# HDMI_Connector.net
KiCad netlist of a schematic drawn in Altium Designer
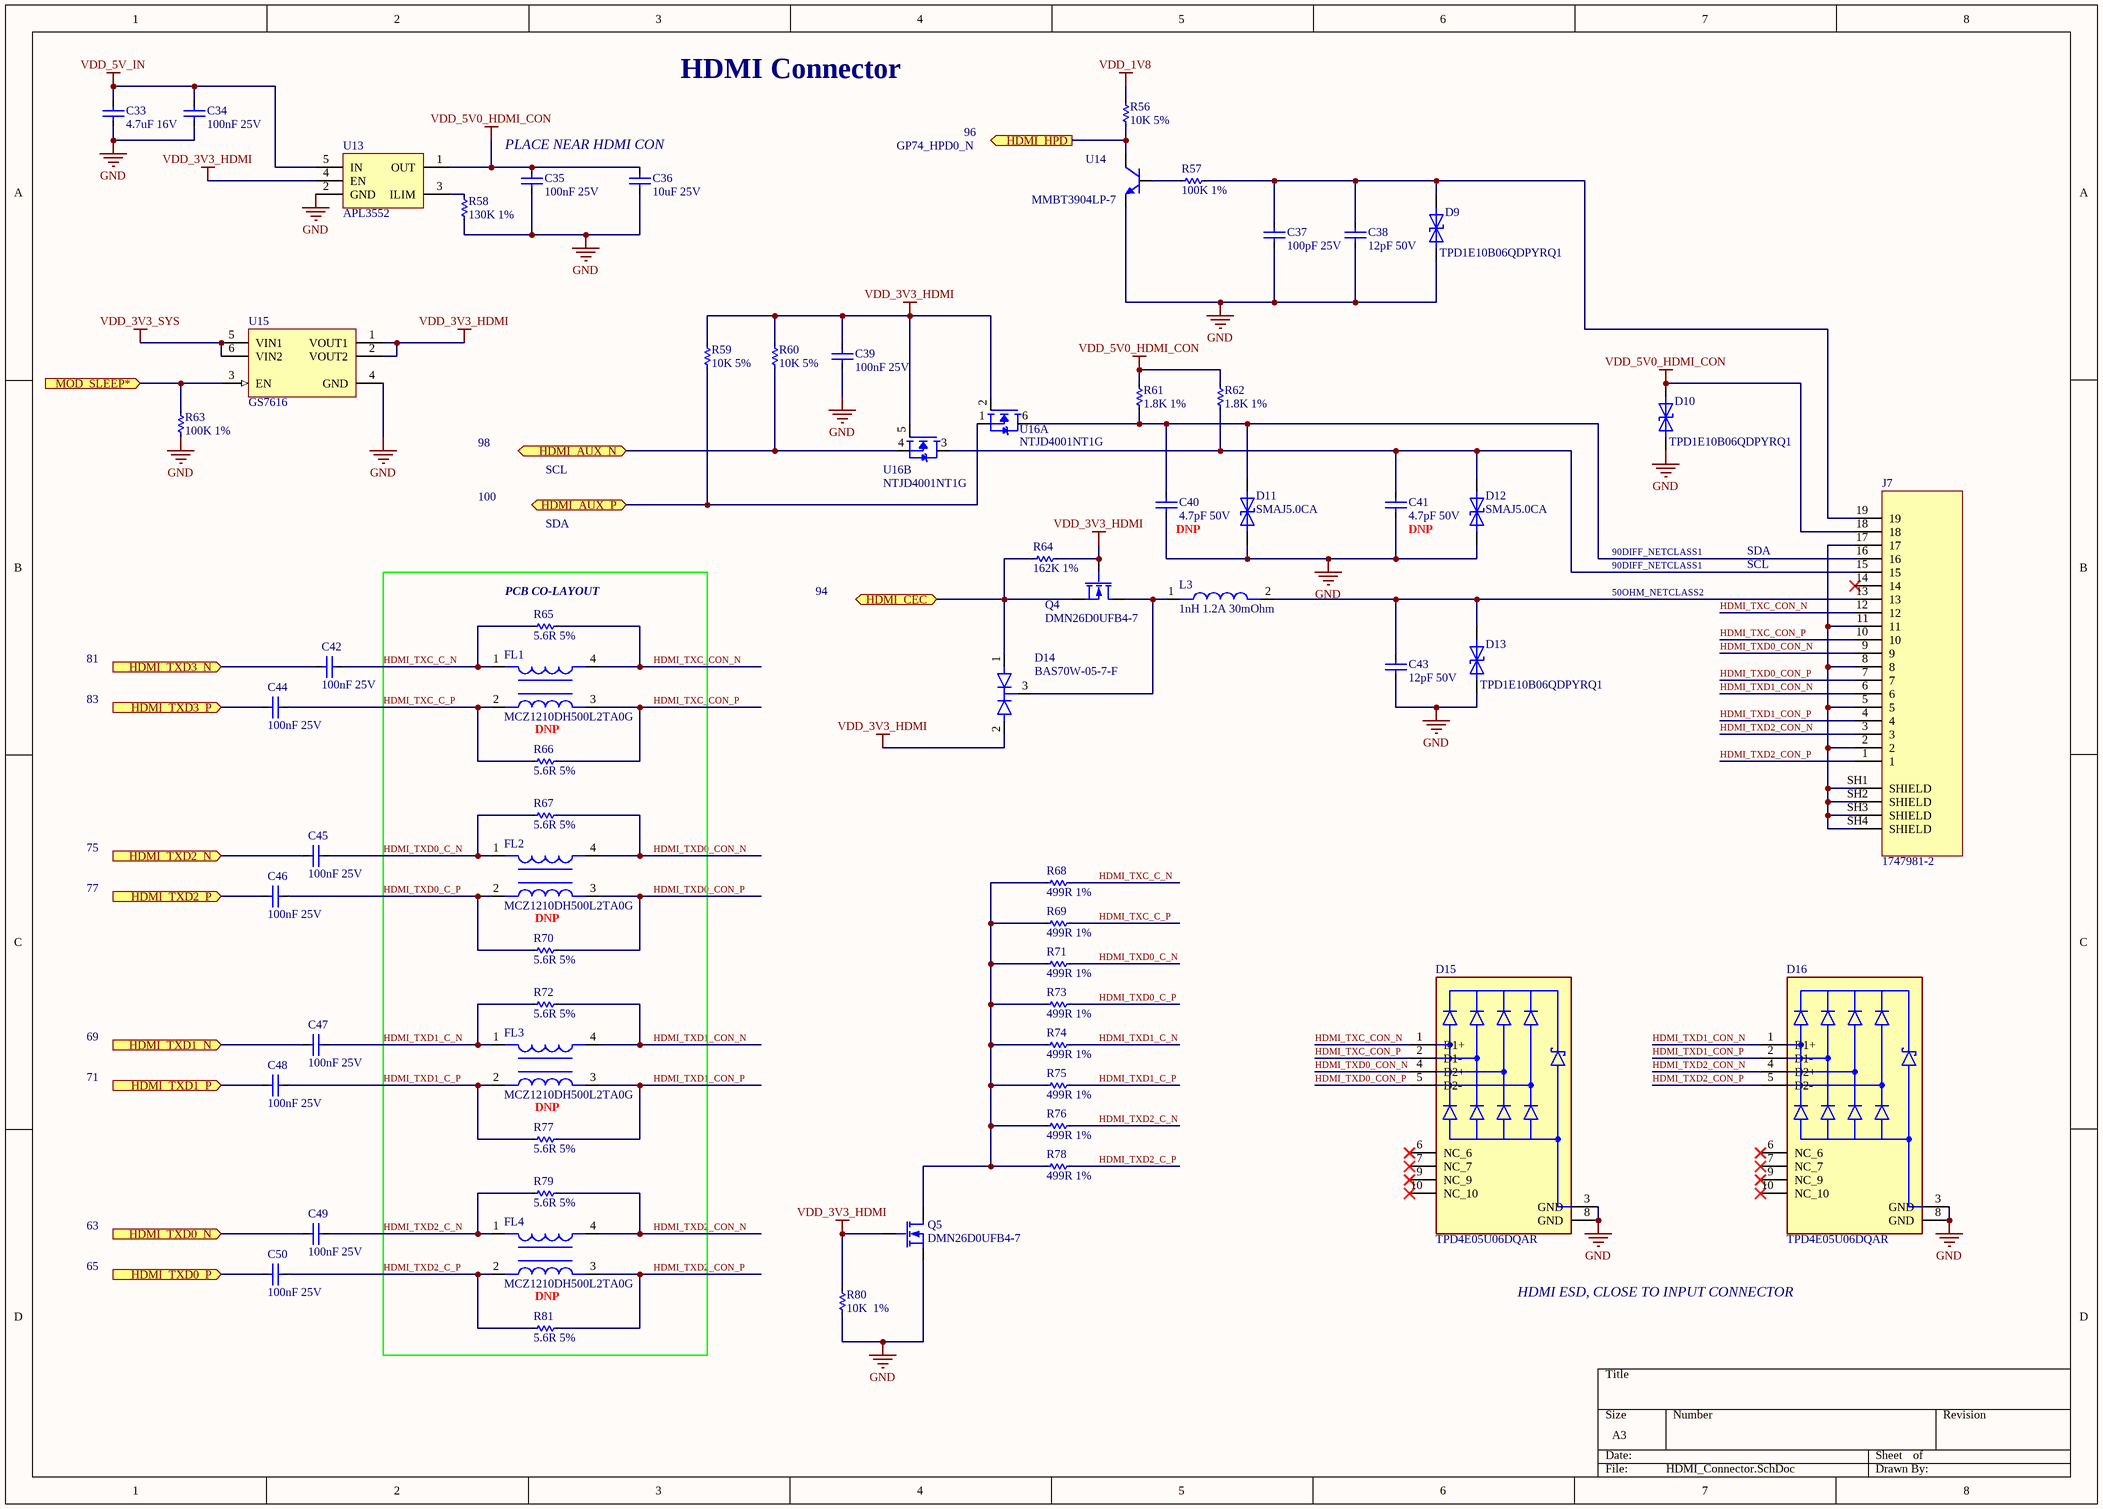
[diagram p0: HDMI_Connector.SchDoc]

(export (version "E")
  (design (tool "Eeschema 10.0.6"))
  (components
    (comp (ref "C33")
      (value "4.7uF 16V")
      (footprint "C0805")
      (description "CAP CER 4.7UF 16V X5R 0805")
      (fields
        (field (name "MANUFACTURER") "Kyocera AVX")
        (field (name "MANUFACTURER PART NUMBER") "0805YD475KAT2A")
      )
      (libsource (lib "GM_Altium_Library") (part "0805YD475KAT2A"))
    )
    (comp (ref "C34")
      (value "100nF 25V")
      (footprint "C0402")
      (description "0402 100 nF 25 V ±10 % Tolerance X7R Surface Mount Multilayer Ceramic Capacitor")
      (fields
        (field (name "MANUFACTURER") "Kyocera AVX")
        (field (name "MANUFACTURER PART NUMBER") "04023C104KAT2A")
      )
      (libsource (lib "GM_Altium_Library") (part "04023C104KAT2A"))
    )
    (comp (ref "C35")
      (value "100nF 25V")
      (footprint "C0402")
      (description "0402 100 nF 25 V ±10 % Tolerance X7R Surface Mount Multilayer Ceramic Capacitor")
      (fields
        (field (name "MANUFACTURER") "Kyocera AVX")
        (field (name "MANUFACTURER PART NUMBER") "04023C104KAT2A")
      )
      (libsource (lib "GM_Altium_Library") (part "04023C104KAT2A"))
    )
    (comp (ref "C36")
      (value "10uF 25V")
      (footprint "C0805")
      (description "0805 10 uF 25 V ±10% Tolerance X5R SMT Multilayer Ceramic Capacitor")
      (fields
        (field (name "MANUFACTURER") "Taiyo Yuden")
        (field (name "MANUFACTURER PART NUMBER") "TMK212BBJ106KG-T")
      )
      (libsource (lib "GM_Altium_Library") (part "TMK212BBJ106KG-T"))
    )
    (comp (ref "C37")
      (value "100pF 25V")
      (footprint "C0402")
      (description "Cap Ceramic 100pF 25V C0G 5% SMD 0402 125C Paper T/R")
      (fields
        (field (name "MANUFACTURER") "KEMET")
        (field (name "MANUFACTURER PART NUMBER") "C0402C101J3GACTU")
      )
      (libsource (lib "GM_Altium_Library") (part "C0402C101J3GACTU"))
    )
    (comp (ref "C38")
      (value "12pF 50V")
      (footprint "C0402")
      (description "0402 12 pF 50 V ±5 % Tolerance NP0 SMT Multilayer Ceramic Capacitor")
      (fields
        (field (name "MANUFACTURER") "Yageo")
        (field (name "MANUFACTURER PART NUMBER") "CC0402JRNPO9BN120")
      )
      (libsource (lib "GM_Altium_Library") (part "CC0402JRNPO9BN120"))
    )
    (comp (ref "C39")
      (value "100nF 25V")
      (footprint "C0402")
      (description "CAP CER 0.1UF 25V X5R 0402 / High Value Multilayer Ceramic Capacitors (High dielectric type)")
      (fields
        (field (name "MANUFACTURER") "Taiyo Yuden")
        (field (name "MANUFACTURER PART NUMBER") "TMK105BJ104KV-F")
      )
      (libsource (lib "GM_Altium_Library") (part "TMK105BJ104KV-F"))
    )
    (comp (ref "C40")
      (value "4.7pF 50V")
      (footprint "C0402")
      (description "Surface Mount Ceramic Multilayer Capacitor 4.7pF 0.25pF C0G 50V 0402 Paper T/R")
      (fields
        (field (name "MANUFACTURER") "Yageo")
        (field (name "MANUFACTURER PART NUMBER") "CC0402CRNPO9BN4R7")
      )
      (libsource (lib "GM_Altium_Library") (part "CC0402CRNPO9BN4R7"))
    )
    (comp (ref "C41")
      (value "4.7pF 50V")
      (footprint "C0402")
      (description "Surface Mount Ceramic Multilayer Capacitor 4.7pF 0.25pF C0G 50V 0402 Paper T/R")
      (fields
        (field (name "MANUFACTURER") "Yageo")
        (field (name "MANUFACTURER PART NUMBER") "CC0402CRNPO9BN4R7")
      )
      (libsource (lib "GM_Altium_Library") (part "CC0402CRNPO9BN4R7"))
    )
    (comp (ref "C42")
      (value "100nF 25V")
      (footprint "C0402")
      (description "0402 100 nF 25 V ±10 % Tolerance X7R Surface Mount Multilayer Ceramic Capacitor")
      (fields
        (field (name "MANUFACTURER") "Kyocera AVX")
        (field (name "MANUFACTURER PART NUMBER") "04023C104KAT2A")
      )
      (libsource (lib "GM_Altium_Library") (part "04023C104KAT2A"))
    )
    (comp (ref "C43")
      (value "12pF 50V")
      (footprint "C0402")
      (description "0402 12 pF 50 V ±5 % Tolerance NP0 SMT Multilayer Ceramic Capacitor")
      (fields
        (field (name "MANUFACTURER") "Yageo")
        (field (name "MANUFACTURER PART NUMBER") "CC0402JRNPO9BN120")
      )
      (libsource (lib "GM_Altium_Library") (part "CC0402JRNPO9BN120"))
    )
    (comp (ref "C44")
      (value "100nF 25V")
      (footprint "C0402")
      (description "0402 100 nF 25 V ±10 % Tolerance X7R Surface Mount Multilayer Ceramic Capacitor")
      (fields
        (field (name "MANUFACTURER") "Kyocera AVX")
        (field (name "MANUFACTURER PART NUMBER") "04023C104KAT2A")
      )
      (libsource (lib "GM_Altium_Library") (part "04023C104KAT2A"))
    )
    (comp (ref "C45")
      (value "100nF 25V")
      (footprint "C0402")
      (description "0402 100 nF 25 V ±10 % Tolerance X7R Surface Mount Multilayer Ceramic Capacitor")
      (fields
        (field (name "MANUFACTURER") "Kyocera AVX")
        (field (name "MANUFACTURER PART NUMBER") "04023C104KAT2A")
      )
      (libsource (lib "GM_Altium_Library") (part "04023C104KAT2A"))
    )
    (comp (ref "C46")
      (value "100nF 25V")
      (footprint "C0402")
      (description "0402 100 nF 25 V ±10 % Tolerance X7R Surface Mount Multilayer Ceramic Capacitor")
      (fields
        (field (name "MANUFACTURER") "Kyocera AVX")
        (field (name "MANUFACTURER PART NUMBER") "04023C104KAT2A")
      )
      (libsource (lib "GM_Altium_Library") (part "04023C104KAT2A"))
    )
    (comp (ref "C47")
      (value "100nF 25V")
      (footprint "C0402")
      (description "0402 100 nF 25 V ±10 % Tolerance X7R Surface Mount Multilayer Ceramic Capacitor")
      (fields
        (field (name "MANUFACTURER") "Kyocera AVX")
        (field (name "MANUFACTURER PART NUMBER") "04023C104KAT2A")
      )
      (libsource (lib "GM_Altium_Library") (part "04023C104KAT2A"))
    )
    (comp (ref "C48")
      (value "100nF 25V")
      (footprint "C0402")
      (description "0402 100 nF 25 V ±10 % Tolerance X7R Surface Mount Multilayer Ceramic Capacitor")
      (fields
        (field (name "MANUFACTURER") "Kyocera AVX")
        (field (name "MANUFACTURER PART NUMBER") "04023C104KAT2A")
      )
      (libsource (lib "GM_Altium_Library") (part "04023C104KAT2A"))
    )
    (comp (ref "C49")
      (value "100nF 25V")
      (footprint "C0402")
      (description "0402 100 nF 25 V ±10 % Tolerance X7R Surface Mount Multilayer Ceramic Capacitor")
      (fields
        (field (name "MANUFACTURER") "Kyocera AVX")
        (field (name "MANUFACTURER PART NUMBER") "04023C104KAT2A")
      )
      (libsource (lib "GM_Altium_Library") (part "04023C104KAT2A"))
    )
    (comp (ref "C50")
      (value "100nF 25V")
      (footprint "C0402")
      (description "0402 100 nF 25 V ±10 % Tolerance X7R Surface Mount Multilayer Ceramic Capacitor")
      (fields
        (field (name "MANUFACTURER") "Kyocera AVX")
        (field (name "MANUFACTURER PART NUMBER") "04023C104KAT2A")
      )
      (libsource (lib "GM_Altium_Library") (part "04023C104KAT2A"))
    )
    (comp (ref "D9")
      (value "TPD1E10B06QDPYRQ1")
      (footprint "2-X1SON (1x.60)")
      (description "Automotive 12-pF, ±5.5V ±30-kV ESD protection diode in 0402 Package 2-X1SON -40 to 125")
      (fields (field (name "MANUFACTURER") "Texas Instruments"))
      (libsource (lib "GM_Altium_Library") (part "TPD1E10B06QDPYRQ1"))
    )
    (comp (ref "D10")
      (value "TPD1E10B06QDPYRQ1")
      (footprint "2-X1SON (1x.60)")
      (description "Automotive 12-pF, ±5.5V ±30-kV ESD protection diode in 0402 Package 2-X1SON -40 to 125")
      (fields (field (name "MANUFACTURER") "Texas Instruments"))
      (libsource (lib "GM_Altium_Library") (part "TPD1E10B06QDPYRQ1"))
    )
    (comp (ref "D11")
      (value "SMAJ5.0CA")
      (footprint "DO-214AC")
      (fields (field (name "MANUFACTURER") "Littelfuse"))
      (libsource (lib "GM_Altium_Library") (part "SMAJ5.0CA"))
    )
    (comp (ref "D12")
      (value "SMAJ5.0CA")
      (footprint "DO-214AC")
      (fields (field (name "MANUFACTURER") "Littelfuse"))
      (libsource (lib "GM_Altium_Library") (part "SMAJ5.0CA"))
    )
    (comp (ref "D13")
      (value "TPD1E10B06QDPYRQ1")
      (footprint "2-X1SON (1x.60)")
      (description "Automotive 12-pF, ±5.5V ±30-kV ESD protection diode in 0402 Package 2-X1SON -40 to 125")
      (fields (field (name "MANUFACTURER") "Texas Instruments"))
      (libsource (lib "GM_Altium_Library") (part "TPD1E10B06QDPYRQ1"))
    )
    (comp (ref "D14")
      (value "BAS70W-05-7-F")
      (footprint "SOT-323")
      (description "DIODE ARRAY SCHOTTKY 70V SOT323")
      (fields (field (name "MANUFACTURER") "Diodes"))
      (libsource (lib "GM_Altium_Library") (part "BAS70W-05-7-F"))
    )
    (comp (ref "D15")
      (value "TPD4E05U06DQAR")
      (footprint "TPD4E05U06DQAR")
      (description "Quad 0.5-pF, 5.5-V, ±12-kV ESD protection diode for USB, HDMI & High Speed Interfaces")
      (fields (field (name "MANUFACTURER") "Texas Instruments"))
      (libsource (lib "GM_Altium_Library") (part "TPD4E05U06DQAR"))
    )
    (comp (ref "D16")
      (value "TPD4E05U06DQAR")
      (footprint "TPD4E05U06DQAR")
      (description "Quad 0.5-pF, 5.5-V, ±12-kV ESD protection diode for USB, HDMI & High Speed Interfaces")
      (fields (field (name "MANUFACTURER") "Texas Instruments"))
      (libsource (lib "GM_Altium_Library") (part "TPD4E05U06DQAR"))
    )
    (comp (ref "FL1")
      (value "MCZ1210DH500L2TA0G")
      (footprint "MCZ1210DH500L2TA0G")
      (description "2 Line Common Mode Choke Surface Mount 50 Ohms 100mA DCR 2.5Ohm")
      (fields (field (name "MANUFACTURER") "TDK"))
      (libsource (lib "GM_Altium_Library") (part "MCZ1210DH500L2TA0G"))
    )
    (comp (ref "FL2")
      (value "MCZ1210DH500L2TA0G")
      (footprint "MCZ1210DH500L2TA0G")
      (description "2 Line Common Mode Choke Surface Mount 50 Ohms 100mA DCR 2.5Ohm")
      (fields (field (name "MANUFACTURER") "TDK"))
      (libsource (lib "GM_Altium_Library") (part "MCZ1210DH500L2TA0G"))
    )
    (comp (ref "FL3")
      (value "MCZ1210DH500L2TA0G")
      (footprint "MCZ1210DH500L2TA0G")
      (description "2 Line Common Mode Choke Surface Mount 50 Ohms 100mA DCR 2.5Ohm")
      (fields (field (name "MANUFACTURER") "TDK"))
      (libsource (lib "GM_Altium_Library") (part "MCZ1210DH500L2TA0G"))
    )
    (comp (ref "FL4")
      (value "MCZ1210DH500L2TA0G")
      (footprint "MCZ1210DH500L2TA0G")
      (description "2 Line Common Mode Choke Surface Mount 50 Ohms 100mA DCR 2.5Ohm")
      (fields (field (name "MANUFACTURER") "TDK"))
      (libsource (lib "GM_Altium_Library") (part "MCZ1210DH500L2TA0G"))
    )
    (comp (ref "J7")
      (value "1747981-2")
      (footprint "1747981-2")
      (description "Conn HDMI RCP 19 POS 0.5mm Solder ST SMD 19 Terminal 1 Port T/R")
      (fields (field (name "MANUFACTURER") "TE Connectivity"))
      (libsource (lib "GM_Altium_Library") (part "1747981-2"))
    )
    (comp (ref "L3")
      (value "1nH 1.2A 30mOhm")
      (footprint "L0402")
      (description "Inductor Chip 1nH 0.1nH Tolerance 2-Pin 0402 Paper T/R")
      (fields
        (field (name "MANUFACTURER") "Murata")
        (field (name "MANUFACTURER PART NUMBER") "LQG15WH1N0B02D")
      )
      (libsource (lib "GM_Altium_Library") (part "LQG15WH1N0B02D"))
    )
    (comp (ref "Q4")
      (value "DMN26D0UFB4-7")
      (footprint "DFN1006-3")
      (description "Single N-Channel 20 V 350 mW Silicon Surface Mount Mosfet - DFN-3")
      (fields (field (name "MANUFACTURER") "Diodes"))
      (libsource (lib "GM_Altium_Library") (part "DMN26D0UFB4-7"))
    )
    (comp (ref "Q5")
      (value "DMN26D0UFB4-7")
      (footprint "DFN1006-3")
      (description "Single N-Channel 20 V 350 mW Silicon Surface Mount Mosfet - DFN-3")
      (fields (field (name "MANUFACTURER") "Diodes"))
      (libsource (lib "GM_Altium_Library") (part "DMN26D0UFB4-7"))
    )
    (comp (ref "R56")
      (value "10K 5%")
      (footprint "R0402")
      (description "Res Thick Film 0402 10K Ohm 5% 0.063W(1/16W) ±100ppm/C Pad SMD T/R")
      (fields
        (field (name "MANUFACTURER") "Yageo")
        (field (name "MANUFACTURER PART NUMBER") "RC0402JR-0710KL")
      )
      (libsource (lib "GM_Altium_Library") (part "RC0402JR-0710KL"))
    )
    (comp (ref "R57")
      (value "100K 1%")
      (footprint "R0402")
      (description "RES SMD 100K OHM 1% 1/16W 0402")
      (fields
        (field (name "MANUFACTURER") "Yageo")
        (field (name "MANUFACTURER PART NUMBER") "RC0402FR-07100KL")
      )
      (libsource (lib "GM_Altium_Library") (part "RC0402FR-07100KL"))
    )
    (comp (ref "R58")
      (value "130K 1%")
      (footprint "R0402")
      (description "Res General Purpose Thick Film 0402 130k Ohm 1% 1/16W ±100ppm/°C Molded Paper T/R")
      (fields
        (field (name "MANUFACTURER") "Yageo")
        (field (name "MANUFACTURER PART NUMBER") "RC0402FR-07130KL")
      )
      (libsource (lib "GM_Altium_Library") (part "RC0402FR-07130KL"))
    )
    (comp (ref "R59")
      (value "10K 5%")
      (footprint "R0402")
      (description "Res Thick Film 0402 10K Ohm 5% 0.063W(1/16W) ±100ppm/C Pad SMD T/R")
      (fields
        (field (name "MANUFACTURER") "Yageo")
        (field (name "MANUFACTURER PART NUMBER") "RC0402JR-0710KL")
      )
      (libsource (lib "GM_Altium_Library") (part "RC0402JR-0710KL"))
    )
    (comp (ref "R60")
      (value "10K 5%")
      (footprint "R0402")
      (description "Res Thick Film 0402 10K Ohm 5% 0.063W(1/16W) ±100ppm/C Pad SMD T/R")
      (fields
        (field (name "MANUFACTURER") "Yageo")
        (field (name "MANUFACTURER PART NUMBER") "RC0402JR-0710KL")
      )
      (libsource (lib "GM_Altium_Library") (part "RC0402JR-0710KL"))
    )
    (comp (ref "R61")
      (value "1.8K 1%")
      (footprint "R0402")
      (description "Res General Purpose Thick Film 0402 1.8K Ohm 1% 1/16W ±100ppm/°C Molded SMD Paper T/R")
      (fields
        (field (name "MANUFACTURER") "Yageo")
        (field (name "MANUFACTURER PART NUMBER") "RC0402FR-071K8L")
      )
      (libsource (lib "GM_Altium_Library") (part "RC0402FR-071K8L"))
    )
    (comp (ref "R62")
      (value "1.8K 1%")
      (footprint "R0402")
      (description "Res General Purpose Thick Film 0402 1.8K Ohm 1% 1/16W ±100ppm/°C Molded SMD Paper T/R")
      (fields
        (field (name "MANUFACTURER") "Yageo")
        (field (name "MANUFACTURER PART NUMBER") "RC0402FR-071K8L")
      )
      (libsource (lib "GM_Altium_Library") (part "RC0402FR-071K8L"))
    )
    (comp (ref "R63")
      (value "100K 1%")
      (footprint "R0402")
      (description "RES SMD 100K OHM 1% 1/16W 0402")
      (fields
        (field (name "MANUFACTURER") "Yageo")
        (field (name "MANUFACTURER PART NUMBER") "RC0402FR-07100KL")
      )
      (libsource (lib "GM_Altium_Library") (part "RC0402FR-07100KL"))
    )
    (comp (ref "R64")
      (value "162K 1%")
      (footprint "R0402")
      (description "Res Thick Film 0402 162K Ohm 1% 1/16W ±100ppm/°C Molded SMD Paper T/R")
      (fields
        (field (name "MANUFACTURER") "Yageo")
        (field (name "MANUFACTURER PART NUMBER") "RC0402FR-07162KL")
      )
      (libsource (lib "GM_Altium_Library") (part "RC0402FR-07162KL"))
    )
    (comp (ref "R65")
      (value "5.6R 5%")
      (footprint "R0402")
      (description "Res Thick Film 0402 5.6 Ohm 5% 1/16W ±200ppm/°C Molded SMD Paper T/R")
      (fields
        (field (name "MANUFACTURER") "Yageo")
        (field (name "MANUFACTURER PART NUMBER") "RC0402JR-075R6L")
      )
      (libsource (lib "GM_Altium_Library") (part "RC0402JR-075R6L"))
    )
    (comp (ref "R66")
      (value "5.6R 5%")
      (footprint "R0402")
      (description "Res Thick Film 0402 5.6 Ohm 5% 1/16W ±200ppm/°C Molded SMD Paper T/R")
      (fields
        (field (name "MANUFACTURER") "Yageo")
        (field (name "MANUFACTURER PART NUMBER") "RC0402JR-075R6L")
      )
      (libsource (lib "GM_Altium_Library") (part "RC0402JR-075R6L"))
    )
    (comp (ref "R67")
      (value "5.6R 5%")
      (footprint "R0402")
      (description "Res Thick Film 0402 5.6 Ohm 5% 1/16W ±200ppm/°C Molded SMD Paper T/R")
      (fields
        (field (name "MANUFACTURER") "Yageo")
        (field (name "MANUFACTURER PART NUMBER") "RC0402JR-075R6L")
      )
      (libsource (lib "GM_Altium_Library") (part "RC0402JR-075R6L"))
    )
    (comp (ref "R68")
      (value "499R 1%")
      (footprint "R0402")
      (description "Res General Purpose Thick Film 0402 499 Ohm 1% 1/16W ±100ppm/°C Molded SMD Paper T/R")
      (fields
        (field (name "MANUFACTURER") "Yageo")
        (field (name "MANUFACTURER PART NUMBER") "RC0402FR-07499RL")
      )
      (libsource (lib "GM_Altium_Library") (part "RC0402FR-07499RL"))
    )
    (comp (ref "R69")
      (value "499R 1%")
      (footprint "R0402")
      (description "Res General Purpose Thick Film 0402 499 Ohm 1% 1/16W ±100ppm/°C Molded SMD Paper T/R")
      (fields
        (field (name "MANUFACTURER") "Yageo")
        (field (name "MANUFACTURER PART NUMBER") "RC0402FR-07499RL")
      )
      (libsource (lib "GM_Altium_Library") (part "RC0402FR-07499RL"))
    )
    (comp (ref "R70")
      (value "5.6R 5%")
      (footprint "R0402")
      (description "Res Thick Film 0402 5.6 Ohm 5% 1/16W ±200ppm/°C Molded SMD Paper T/R")
      (fields
        (field (name "MANUFACTURER") "Yageo")
        (field (name "MANUFACTURER PART NUMBER") "RC0402JR-075R6L")
      )
      (libsource (lib "GM_Altium_Library") (part "RC0402JR-075R6L"))
    )
    (comp (ref "R71")
      (value "499R 1%")
      (footprint "R0402")
      (description "Res General Purpose Thick Film 0402 499 Ohm 1% 1/16W ±100ppm/°C Molded SMD Paper T/R")
      (fields
        (field (name "MANUFACTURER") "Yageo")
        (field (name "MANUFACTURER PART NUMBER") "RC0402FR-07499RL")
      )
      (libsource (lib "GM_Altium_Library") (part "RC0402FR-07499RL"))
    )
    (comp (ref "R72")
      (value "5.6R 5%")
      (footprint "R0402")
      (description "Res Thick Film 0402 5.6 Ohm 5% 1/16W ±200ppm/°C Molded SMD Paper T/R")
      (fields
        (field (name "MANUFACTURER") "Yageo")
        (field (name "MANUFACTURER PART NUMBER") "RC0402JR-075R6L")
      )
      (libsource (lib "GM_Altium_Library") (part "RC0402JR-075R6L"))
    )
    (comp (ref "R73")
      (value "499R 1%")
      (footprint "R0402")
      (description "Res General Purpose Thick Film 0402 499 Ohm 1% 1/16W ±100ppm/°C Molded SMD Paper T/R")
      (fields
        (field (name "MANUFACTURER") "Yageo")
        (field (name "MANUFACTURER PART NUMBER") "RC0402FR-07499RL")
      )
      (libsource (lib "GM_Altium_Library") (part "RC0402FR-07499RL"))
    )
    (comp (ref "R74")
      (value "499R 1%")
      (footprint "R0402")
      (description "Res General Purpose Thick Film 0402 499 Ohm 1% 1/16W ±100ppm/°C Molded SMD Paper T/R")
      (fields
        (field (name "MANUFACTURER") "Yageo")
        (field (name "MANUFACTURER PART NUMBER") "RC0402FR-07499RL")
      )
      (libsource (lib "GM_Altium_Library") (part "RC0402FR-07499RL"))
    )
    (comp (ref "R75")
      (value "499R 1%")
      (footprint "R0402")
      (description "Res General Purpose Thick Film 0402 499 Ohm 1% 1/16W ±100ppm/°C Molded SMD Paper T/R")
      (fields
        (field (name "MANUFACTURER") "Yageo")
        (field (name "MANUFACTURER PART NUMBER") "RC0402FR-07499RL")
      )
      (libsource (lib "GM_Altium_Library") (part "RC0402FR-07499RL"))
    )
    (comp (ref "R76")
      (value "499R 1%")
      (footprint "R0402")
      (description "Res General Purpose Thick Film 0402 499 Ohm 1% 1/16W ±100ppm/°C Molded SMD Paper T/R")
      (fields
        (field (name "MANUFACTURER") "Yageo")
        (field (name "MANUFACTURER PART NUMBER") "RC0402FR-07499RL")
      )
      (libsource (lib "GM_Altium_Library") (part "RC0402FR-07499RL"))
    )
    (comp (ref "R77")
      (value "5.6R 5%")
      (footprint "R0402")
      (description "Res Thick Film 0402 5.6 Ohm 5% 1/16W ±200ppm/°C Molded SMD Paper T/R")
      (fields
        (field (name "MANUFACTURER") "Yageo")
        (field (name "MANUFACTURER PART NUMBER") "RC0402JR-075R6L")
      )
      (libsource (lib "GM_Altium_Library") (part "RC0402JR-075R6L"))
    )
    (comp (ref "R78")
      (value "499R 1%")
      (footprint "R0402")
      (description "Res General Purpose Thick Film 0402 499 Ohm 1% 1/16W ±100ppm/°C Molded SMD Paper T/R")
      (fields
        (field (name "MANUFACTURER") "Yageo")
        (field (name "MANUFACTURER PART NUMBER") "RC0402FR-07499RL")
      )
      (libsource (lib "GM_Altium_Library") (part "RC0402FR-07499RL"))
    )
    (comp (ref "R79")
      (value "5.6R 5%")
      (footprint "R0402")
      (description "Res Thick Film 0402 5.6 Ohm 5% 1/16W ±200ppm/°C Molded SMD Paper T/R")
      (fields
        (field (name "MANUFACTURER") "Yageo")
        (field (name "MANUFACTURER PART NUMBER") "RC0402JR-075R6L")
      )
      (libsource (lib "GM_Altium_Library") (part "RC0402JR-075R6L"))
    )
    (comp (ref "R80")
      (value "10K  1%")
      (footprint "R0402")
      (description "Res General Purpose Thick Film 0402 10K Ohm 1% 1/16W ±100ppm/°C Molded SMD Paper T/R")
      (fields
        (field (name "MANUFACTURER") "Yageo")
        (field (name "MANUFACTURER PART NUMBER") "RC0402FR-0710KP")
      )
      (libsource (lib "GM_Altium_Library") (part "RC0402FR-0710KP"))
    )
    (comp (ref "R81")
      (value "5.6R 5%")
      (footprint "R0402")
      (description "Res Thick Film 0402 5.6 Ohm 5% 1/16W ±200ppm/°C Molded SMD Paper T/R")
      (fields
        (field (name "MANUFACTURER") "Yageo")
        (field (name "MANUFACTURER PART NUMBER") "RC0402JR-075R6L")
      )
      (libsource (lib "GM_Altium_Library") (part "RC0402JR-075R6L"))
    )
    (comp (ref "U13")
      (value "APL3552")
      (footprint "SOT23-5")
      (description "The APL3552 series of power switches integrate a 62mW N-channel MOSFET.")
      (libsource (lib "GM_Altium_Library") (part "APL3552"))
    )
    (comp (ref "U14")
      (value "MMBT3904LP-7")
      (footprint "DFN1006-3")
      (description "TRANS NPN 40V 0.2A DFN1006-3")
      (fields (field (name "MANUFACTURER") "Diodes"))
      (libsource (lib "GM_Altium_Library") (part "MMBT3904LP-7"))
    )
    (comp (ref "U15")
      (value "GS7616")
      (footprint "SOT-363")
      (libsource (lib "GM_Altium_Library") (part "GS7616"))
    )
    (comp (ref "U16")
      (value "NTJD4001NT1G")
      (footprint "SOT-363")
      (description "MOSFET 2N-CH 30V 0.25A SOT-363")
      (fields (field (name "MANUFACTURER") "ON Semiconductor"))
      (libsource (lib "GM_Altium_Library") (part "NTJD4001NT1G"))
    )
  )
  (nets
    (net (code "1") (name "/HDMI_AUX_N") (class "Default")
      (node (ref "R60") (pin "1") (pinfunction "1_1") (pintype "passive"))
      (node (ref "U16") (pin "4") (pinfunction "S2_4") (pintype "passive"))
    )
    (net (code "2") (name "/HDMI_AUX_P") (class "Default")
      (node (ref "R59") (pin "1") (pinfunction "1_1") (pintype "passive"))
      (node (ref "U16") (pin "1") (pinfunction "S1_1") (pintype "passive"))
    )
    (net (code "3") (name "/HDMI_CEC") (class "Default")
      (node (ref "D14") (pin "1") (pinfunction "1_1") (pintype "passive"))
      (node (ref "Q4") (pin "2") (pinfunction "S_2") (pintype "passive"))
      (node (ref "R64") (pin "1") (pinfunction "1_1") (pintype "passive"))
    )
    (net (code "4") (name "/HDMI_HPD") (class "Default")
      (node (ref "R56") (pin "1") (pinfunction "1_1") (pintype "passive"))
      (node (ref "U14") (pin "3") (pinfunction "C_3") (pintype "passive"))
    )
    (net (code "5") (name "/HDMI_TXC_CON_N") (class "Default")
      (node (ref "D15") (pin "1") (pinfunction "D1+_1") (pintype "passive"))
      (node (ref "FL1") (pin "4") (pinfunction "4_4") (pintype "passive"))
      (node (ref "J7") (pin "12") (pinfunction "12_12") (pintype "passive"))
      (node (ref "R65") (pin "2") (pinfunction "2_2") (pintype "passive"))
    )
    (net (code "6") (name "/HDMI_TXC_CON_P") (class "Default")
      (node (ref "D15") (pin "2") (pinfunction "D1-_2") (pintype "passive"))
      (node (ref "FL1") (pin "3") (pinfunction "3_3") (pintype "passive"))
      (node (ref "J7") (pin "10") (pinfunction "10_10") (pintype "passive"))
      (node (ref "R66") (pin "2") (pinfunction "2_2") (pintype "passive"))
    )
    (net (code "7") (name "/HDMI_TXC_C_N") (class "Default")
      (node (ref "C42") (pin "2") (pinfunction "2_2") (pintype "passive"))
      (node (ref "FL1") (pin "1") (pinfunction "1_1") (pintype "passive"))
      (node (ref "R65") (pin "1") (pinfunction "1_1") (pintype "passive"))
      (node (ref "R68") (pin "2") (pinfunction "2_2") (pintype "passive"))
    )
    (net (code "8") (name "/HDMI_TXC_C_P") (class "Default")
      (node (ref "C44") (pin "2") (pinfunction "2_2") (pintype "passive"))
      (node (ref "FL1") (pin "2") (pinfunction "2_2") (pintype "passive"))
      (node (ref "R66") (pin "1") (pinfunction "1_1") (pintype "passive"))
      (node (ref "R69") (pin "2") (pinfunction "2_2") (pintype "passive"))
    )
    (net (code "9") (name "/HDMI_TXD0_CON_N") (class "Default")
      (node (ref "D15") (pin "4") (pinfunction "D2+_4") (pintype "passive"))
      (node (ref "FL2") (pin "4") (pinfunction "4_4") (pintype "passive"))
      (node (ref "J7") (pin "9") (pinfunction "9_9") (pintype "passive"))
      (node (ref "R67") (pin "2") (pinfunction "2_2") (pintype "passive"))
    )
    (net (code "10") (name "/HDMI_TXD0_CON_P") (class "Default")
      (node (ref "D15") (pin "5") (pinfunction "D2-_5") (pintype "passive"))
      (node (ref "FL2") (pin "3") (pinfunction "3_3") (pintype "passive"))
      (node (ref "J7") (pin "7") (pinfunction "7_7") (pintype "passive"))
      (node (ref "R70") (pin "2") (pinfunction "2_2") (pintype "passive"))
    )
    (net (code "11") (name "/HDMI_TXD0_C_N") (class "Default")
      (node (ref "C45") (pin "2") (pinfunction "2_2") (pintype "passive"))
      (node (ref "FL2") (pin "1") (pinfunction "1_1") (pintype "passive"))
      (node (ref "R67") (pin "1") (pinfunction "1_1") (pintype "passive"))
      (node (ref "R71") (pin "2") (pinfunction "2_2") (pintype "passive"))
    )
    (net (code "12") (name "/HDMI_TXD0_C_P") (class "Default")
      (node (ref "C46") (pin "2") (pinfunction "2_2") (pintype "passive"))
      (node (ref "FL2") (pin "2") (pinfunction "2_2") (pintype "passive"))
      (node (ref "R70") (pin "1") (pinfunction "1_1") (pintype "passive"))
      (node (ref "R73") (pin "2") (pinfunction "2_2") (pintype "passive"))
    )
    (net (code "13") (name "/HDMI_TXD0_N") (class "Default")
      (node (ref "C49") (pin "1") (pinfunction "1_1") (pintype "passive"))
    )
    (net (code "14") (name "/HDMI_TXD0_P") (class "Default")
      (node (ref "C50") (pin "1") (pinfunction "1_1") (pintype "passive"))
    )
    (net (code "15") (name "/HDMI_TXD1_CON_N") (class "Default")
      (node (ref "D16") (pin "1") (pinfunction "D1+_1") (pintype "passive"))
      (node (ref "FL3") (pin "4") (pinfunction "4_4") (pintype "passive"))
      (node (ref "J7") (pin "6") (pinfunction "6_6") (pintype "passive"))
      (node (ref "R72") (pin "2") (pinfunction "2_2") (pintype "passive"))
    )
    (net (code "16") (name "/HDMI_TXD1_CON_P") (class "Default")
      (node (ref "D16") (pin "2") (pinfunction "D1-_2") (pintype "passive"))
      (node (ref "FL3") (pin "3") (pinfunction "3_3") (pintype "passive"))
      (node (ref "J7") (pin "4") (pinfunction "4_4") (pintype "passive"))
      (node (ref "R77") (pin "2") (pinfunction "2_2") (pintype "passive"))
    )
    (net (code "17") (name "/HDMI_TXD1_C_N") (class "Default")
      (node (ref "C47") (pin "2") (pinfunction "2_2") (pintype "passive"))
      (node (ref "FL3") (pin "1") (pinfunction "1_1") (pintype "passive"))
      (node (ref "R72") (pin "1") (pinfunction "1_1") (pintype "passive"))
      (node (ref "R74") (pin "2") (pinfunction "2_2") (pintype "passive"))
    )
    (net (code "18") (name "/HDMI_TXD1_C_P") (class "Default")
      (node (ref "C48") (pin "2") (pinfunction "2_2") (pintype "passive"))
      (node (ref "FL3") (pin "2") (pinfunction "2_2") (pintype "passive"))
      (node (ref "R75") (pin "2") (pinfunction "2_2") (pintype "passive"))
      (node (ref "R77") (pin "1") (pinfunction "1_1") (pintype "passive"))
    )
    (net (code "19") (name "/HDMI_TXD1_N") (class "Default")
      (node (ref "C47") (pin "1") (pinfunction "1_1") (pintype "passive"))
    )
    (net (code "20") (name "/HDMI_TXD1_P") (class "Default")
      (node (ref "C48") (pin "1") (pinfunction "1_1") (pintype "passive"))
    )
    (net (code "21") (name "/HDMI_TXD2_CON_N") (class "Default")
      (node (ref "D16") (pin "4") (pinfunction "D2+_4") (pintype "passive"))
      (node (ref "FL4") (pin "4") (pinfunction "4_4") (pintype "passive"))
      (node (ref "J7") (pin "3") (pinfunction "3_3") (pintype "passive"))
      (node (ref "R79") (pin "2") (pinfunction "2_2") (pintype "passive"))
    )
    (net (code "22") (name "/HDMI_TXD2_CON_P") (class "Default")
      (node (ref "D16") (pin "5") (pinfunction "D2-_5") (pintype "passive"))
      (node (ref "FL4") (pin "3") (pinfunction "3_3") (pintype "passive"))
      (node (ref "J7") (pin "1") (pinfunction "1_1") (pintype "passive"))
      (node (ref "R81") (pin "2") (pinfunction "2_2") (pintype "passive"))
    )
    (net (code "23") (name "/HDMI_TXD2_C_N") (class "Default")
      (node (ref "C49") (pin "2") (pinfunction "2_2") (pintype "passive"))
      (node (ref "FL4") (pin "1") (pinfunction "1_1") (pintype "passive"))
      (node (ref "R76") (pin "2") (pinfunction "2_2") (pintype "passive"))
      (node (ref "R79") (pin "1") (pinfunction "1_1") (pintype "passive"))
    )
    (net (code "24") (name "/HDMI_TXD2_C_P") (class "Default")
      (node (ref "C50") (pin "2") (pinfunction "2_2") (pintype "passive"))
      (node (ref "FL4") (pin "2") (pinfunction "2_2") (pintype "passive"))
      (node (ref "R78") (pin "2") (pinfunction "2_2") (pintype "passive"))
      (node (ref "R81") (pin "1") (pinfunction "1_1") (pintype "passive"))
    )
    (net (code "25") (name "/HDMI_TXD2_N") (class "Default")
      (node (ref "C45") (pin "1") (pinfunction "1_1") (pintype "passive"))
    )
    (net (code "26") (name "/HDMI_TXD2_P") (class "Default")
      (node (ref "C46") (pin "1") (pinfunction "1_1") (pintype "passive"))
    )
    (net (code "27") (name "/HDMI_TXD3_N") (class "Default")
      (node (ref "C42") (pin "1") (pinfunction "1_1") (pintype "passive"))
    )
    (net (code "28") (name "/HDMI_TXD3_P") (class "Default")
      (node (ref "C44") (pin "1") (pinfunction "1_1") (pintype "passive"))
    )
    (net (code "29") (name "/MOD_SLEEP*") (class "Default")
      (node (ref "R63") (pin "2") (pinfunction "2_2") (pintype "passive"))
      (node (ref "U15") (pin "3") (pinfunction "EN_3") (pintype "input"))
    )
    (net (code "30") (name "GND") (class "Default")
      (node (ref "C33") (pin "1") (pinfunction "1_1") (pintype "passive"))
      (node (ref "C34") (pin "1") (pinfunction "1_1") (pintype "passive"))
      (node (ref "C35") (pin "1") (pinfunction "1_1") (pintype "passive"))
      (node (ref "C36") (pin "1") (pinfunction "1_1") (pintype "passive"))
      (node (ref "C37") (pin "1") (pinfunction "1_1") (pintype "passive"))
      (node (ref "C38") (pin "1") (pinfunction "1_1") (pintype "passive"))
      (node (ref "C39") (pin "1") (pinfunction "1_1") (pintype "passive"))
      (node (ref "C40") (pin "1") (pinfunction "1_1") (pintype "passive"))
      (node (ref "C41") (pin "1") (pinfunction "1_1") (pintype "passive"))
      (node (ref "C43") (pin "1") (pinfunction "1_1") (pintype "passive"))
      (node (ref "D10") (pin "1") (pinfunction "1_1") (pintype "passive"))
      (node (ref "D11") (pin "C") (pinfunction "C_C") (pintype "passive"))
      (node (ref "D12") (pin "C") (pinfunction "C_C") (pintype "passive"))
      (node (ref "D13") (pin "1") (pinfunction "1_1") (pintype "passive"))
      (node (ref "D15") (pin "3") (pinfunction "GND_3") (pintype "power_in"))
      (node (ref "D15") (pin "8") (pinfunction "GND_8") (pintype "power_in"))
      (node (ref "D16") (pin "3") (pinfunction "GND_3") (pintype "power_in"))
      (node (ref "D16") (pin "8") (pinfunction "GND_8") (pintype "power_in"))
      (node (ref "D9") (pin "1") (pinfunction "1_1") (pintype "passive"))
      (node (ref "Q5") (pin "2") (pinfunction "S_2") (pintype "passive"))
      (node (ref "R58") (pin "1") (pinfunction "1_1") (pintype "passive"))
      (node (ref "R63") (pin "1") (pinfunction "1_1") (pintype "passive"))
      (node (ref "R80") (pin "1") (pinfunction "1_1") (pintype "passive"))
      (node (ref "U13") (pin "2") (pinfunction "GND_2") (pintype "power_in"))
      (node (ref "U14") (pin "2") (pinfunction "E_2") (pintype "passive"))
      (node (ref "U15") (pin "4") (pinfunction "GND_4") (pintype "power_in"))
    )
    (net (code "31") (name "Net-(C37-Pad2)") (class "Default")
      (node (ref "C37") (pin "2") (pinfunction "2_2") (pintype "passive"))
      (node (ref "C38") (pin "2") (pinfunction "2_2") (pintype "passive"))
      (node (ref "D9") (pin "2") (pinfunction "2_2") (pintype "passive"))
      (node (ref "J7") (pin "19") (pinfunction "19_19") (pintype "passive"))
      (node (ref "R57") (pin "2") (pinfunction "2_2") (pintype "passive"))
    )
    (net (code "32") (name "Net-(C43-Pad2)") (class "Default")
      (node (ref "C43") (pin "2") (pinfunction "2_2") (pintype "passive"))
      (node (ref "D13") (pin "2") (pinfunction "2_2") (pintype "passive"))
      (node (ref "J7") (pin "13") (pinfunction "13_13") (pintype "passive"))
      (node (ref "L3") (pin "2") (pinfunction "2_2") (pintype "passive"))
    )
    (net (code "33") (name "Net-(J7-Pad11)") (class "Default")
      (node (ref "J7") (pin "11") (pinfunction "11_11") (pintype "passive"))
      (node (ref "J7") (pin "17") (pinfunction "17_17") (pintype "passive"))
      (node (ref "J7") (pin "2") (pinfunction "2_2") (pintype "passive"))
      (node (ref "J7") (pin "5") (pinfunction "5_5") (pintype "passive"))
      (node (ref "J7") (pin "8") (pinfunction "8_8") (pintype "passive"))
      (node (ref "J7") (pin "SH1") (pinfunction "SHIELD_SH1") (pintype "passive"))
      (node (ref "J7") (pin "SH2") (pinfunction "SHIELD_SH2") (pintype "passive"))
      (node (ref "J7") (pin "SH3") (pinfunction "SHIELD_SH3") (pintype "passive"))
      (node (ref "J7") (pin "SH4") (pinfunction "SHIELD_SH4") (pintype "passive"))
    )
    (net (code "34") (name "Net-(Q4-D)") (class "Default")
      (node (ref "D14") (pin "3") (pinfunction "3_3") (pintype "passive"))
      (node (ref "L3") (pin "1") (pinfunction "1_1") (pintype "passive"))
      (node (ref "Q4") (pin "3") (pinfunction "D_3") (pintype "passive"))
    )
    (net (code "35") (name "Net-(Q5-D)") (class "Default")
      (node (ref "Q5") (pin "3") (pinfunction "D_3") (pintype "passive"))
      (node (ref "R68") (pin "1") (pinfunction "1_1") (pintype "passive"))
      (node (ref "R69") (pin "1") (pinfunction "1_1") (pintype "passive"))
      (node (ref "R71") (pin "1") (pinfunction "1_1") (pintype "passive"))
      (node (ref "R73") (pin "1") (pinfunction "1_1") (pintype "passive"))
      (node (ref "R74") (pin "1") (pinfunction "1_1") (pintype "passive"))
      (node (ref "R75") (pin "1") (pinfunction "1_1") (pintype "passive"))
      (node (ref "R76") (pin "1") (pinfunction "1_1") (pintype "passive"))
      (node (ref "R78") (pin "1") (pinfunction "1_1") (pintype "passive"))
    )
    (net (code "36") (name "Net-(U13-ILIM)") (class "Default")
      (node (ref "R58") (pin "2") (pinfunction "2_2") (pintype "passive"))
      (node (ref "U13") (pin "3") (pinfunction "ILIM_3") (pintype "passive"))
    )
    (net (code "37") (name "Net-(U14-B)") (class "Default")
      (node (ref "R57") (pin "1") (pinfunction "1_1") (pintype "passive"))
      (node (ref "U14") (pin "1") (pinfunction "B_1") (pintype "passive"))
    )
    (net (code "38") (name "Net-(U16A-D1)") (class "Default")
      (node (ref "C40") (pin "2") (pinfunction "2_2") (pintype "passive"))
      (node (ref "D11") (pin "A") (pinfunction "A_A") (pintype "passive"))
      (node (ref "J7") (pin "16") (pinfunction "16_16") (pintype "passive"))
      (node (ref "R61") (pin "1") (pinfunction "1_1") (pintype "passive"))
      (node (ref "U16") (pin "6") (pinfunction "D1_6") (pintype "passive"))
    )
    (net (code "39") (name "Net-(U16B-D2)") (class "Default")
      (node (ref "C41") (pin "2") (pinfunction "2_2") (pintype "passive"))
      (node (ref "D12") (pin "A") (pinfunction "A_A") (pintype "passive"))
      (node (ref "J7") (pin "15") (pinfunction "15_15") (pintype "passive"))
      (node (ref "R62") (pin "1") (pinfunction "1_1") (pintype "passive"))
      (node (ref "U16") (pin "3") (pinfunction "D2_3") (pintype "passive"))
    )
    (net (code "40") (name "VDD_1V8") (class "Default")
      (node (ref "R56") (pin "2") (pinfunction "2_2") (pintype "passive"))
    )
    (net (code "41") (name "VDD_3V3_HDMI") (class "Default")
      (node (ref "C39") (pin "2") (pinfunction "2_2") (pintype "passive"))
      (node (ref "D14") (pin "2") (pinfunction "2_2") (pintype "passive"))
      (node (ref "Q4") (pin "1") (pinfunction "G_1") (pintype "passive"))
      (node (ref "Q5") (pin "1") (pinfunction "G_1") (pintype "passive"))
      (node (ref "R59") (pin "2") (pinfunction "2_2") (pintype "passive"))
      (node (ref "R60") (pin "2") (pinfunction "2_2") (pintype "passive"))
      (node (ref "R64") (pin "2") (pinfunction "2_2") (pintype "passive"))
      (node (ref "R80") (pin "2") (pinfunction "2_2") (pintype "passive"))
      (node (ref "U13") (pin "4") (pinfunction "EN_4") (pintype "passive"))
      (node (ref "U15") (pin "1") (pinfunction "VOUT1_1") (pintype "power_in"))
      (node (ref "U15") (pin "2") (pinfunction "VOUT2_2") (pintype "power_in"))
      (node (ref "U16") (pin "2") (pinfunction "G1_2") (pintype "passive"))
      (node (ref "U16") (pin "5") (pinfunction "G2_5") (pintype "passive"))
    )
    (net (code "42") (name "VDD_3V3_SYS") (class "Default")
      (node (ref "U15") (pin "5") (pinfunction "VIN1_5") (pintype "power_in"))
      (node (ref "U15") (pin "6") (pinfunction "VIN2_6") (pintype "power_in"))
    )
    (net (code "43") (name "VDD_5V0_HDMI_CON") (class "Default")
      (node (ref "C35") (pin "2") (pinfunction "2_2") (pintype "passive"))
      (node (ref "C36") (pin "2") (pinfunction "2_2") (pintype "passive"))
      (node (ref "D10") (pin "2") (pinfunction "2_2") (pintype "passive"))
      (node (ref "J7") (pin "18") (pinfunction "18_18") (pintype "passive"))
      (node (ref "R61") (pin "2") (pinfunction "2_2") (pintype "passive"))
      (node (ref "R62") (pin "2") (pinfunction "2_2") (pintype "passive"))
      (node (ref "U13") (pin "1") (pinfunction "OUT_1") (pintype "passive"))
    )
    (net (code "44") (name "VDD_5V_IN") (class "Default")
      (node (ref "C33") (pin "2") (pinfunction "2_2") (pintype "passive"))
      (node (ref "C34") (pin "2") (pinfunction "2_2") (pintype "passive"))
      (node (ref "U13") (pin "5") (pinfunction "IN_5") (pintype "power_in"))
    )
    (net (code "45") (name "unconnected-(D15-NC_6-Pad6)") (class "Default")
      (node (ref "D15") (pin "6") (pinfunction "NC_6_6") (pintype "passive+no_connect"))
    )
    (net (code "46") (name "unconnected-(D15-NC_7-Pad7)") (class "Default")
      (node (ref "D15") (pin "7") (pinfunction "NC_7_7") (pintype "passive+no_connect"))
    )
    (net (code "47") (name "unconnected-(D15-NC_9-Pad9)") (class "Default")
      (node (ref "D15") (pin "9") (pinfunction "NC_9_9") (pintype "passive+no_connect"))
    )
    (net (code "48") (name "unconnected-(D15-NC_10-Pad10)") (class "Default")
      (node (ref "D15") (pin "10") (pinfunction "NC_10_10") (pintype "passive+no_connect"))
    )
    (net (code "49") (name "unconnected-(D16-NC_6-Pad6)") (class "Default")
      (node (ref "D16") (pin "6") (pinfunction "NC_6_6") (pintype "passive+no_connect"))
    )
    (net (code "50") (name "unconnected-(D16-NC_7-Pad7)") (class "Default")
      (node (ref "D16") (pin "7") (pinfunction "NC_7_7") (pintype "passive+no_connect"))
    )
    (net (code "51") (name "unconnected-(D16-NC_9-Pad9)") (class "Default")
      (node (ref "D16") (pin "9") (pinfunction "NC_9_9") (pintype "passive+no_connect"))
    )
    (net (code "52") (name "unconnected-(D16-NC_10-Pad10)") (class "Default")
      (node (ref "D16") (pin "10") (pinfunction "NC_10_10") (pintype "passive+no_connect"))
    )
    (net (code "53") (name "unconnected-(J7-Pad14)") (class "Default")
      (node (ref "J7") (pin "14") (pinfunction "14_14") (pintype "passive+no_connect"))
    )
  )
)
